# main.net
KiCad netlist of a schematic drawn in EAGLE
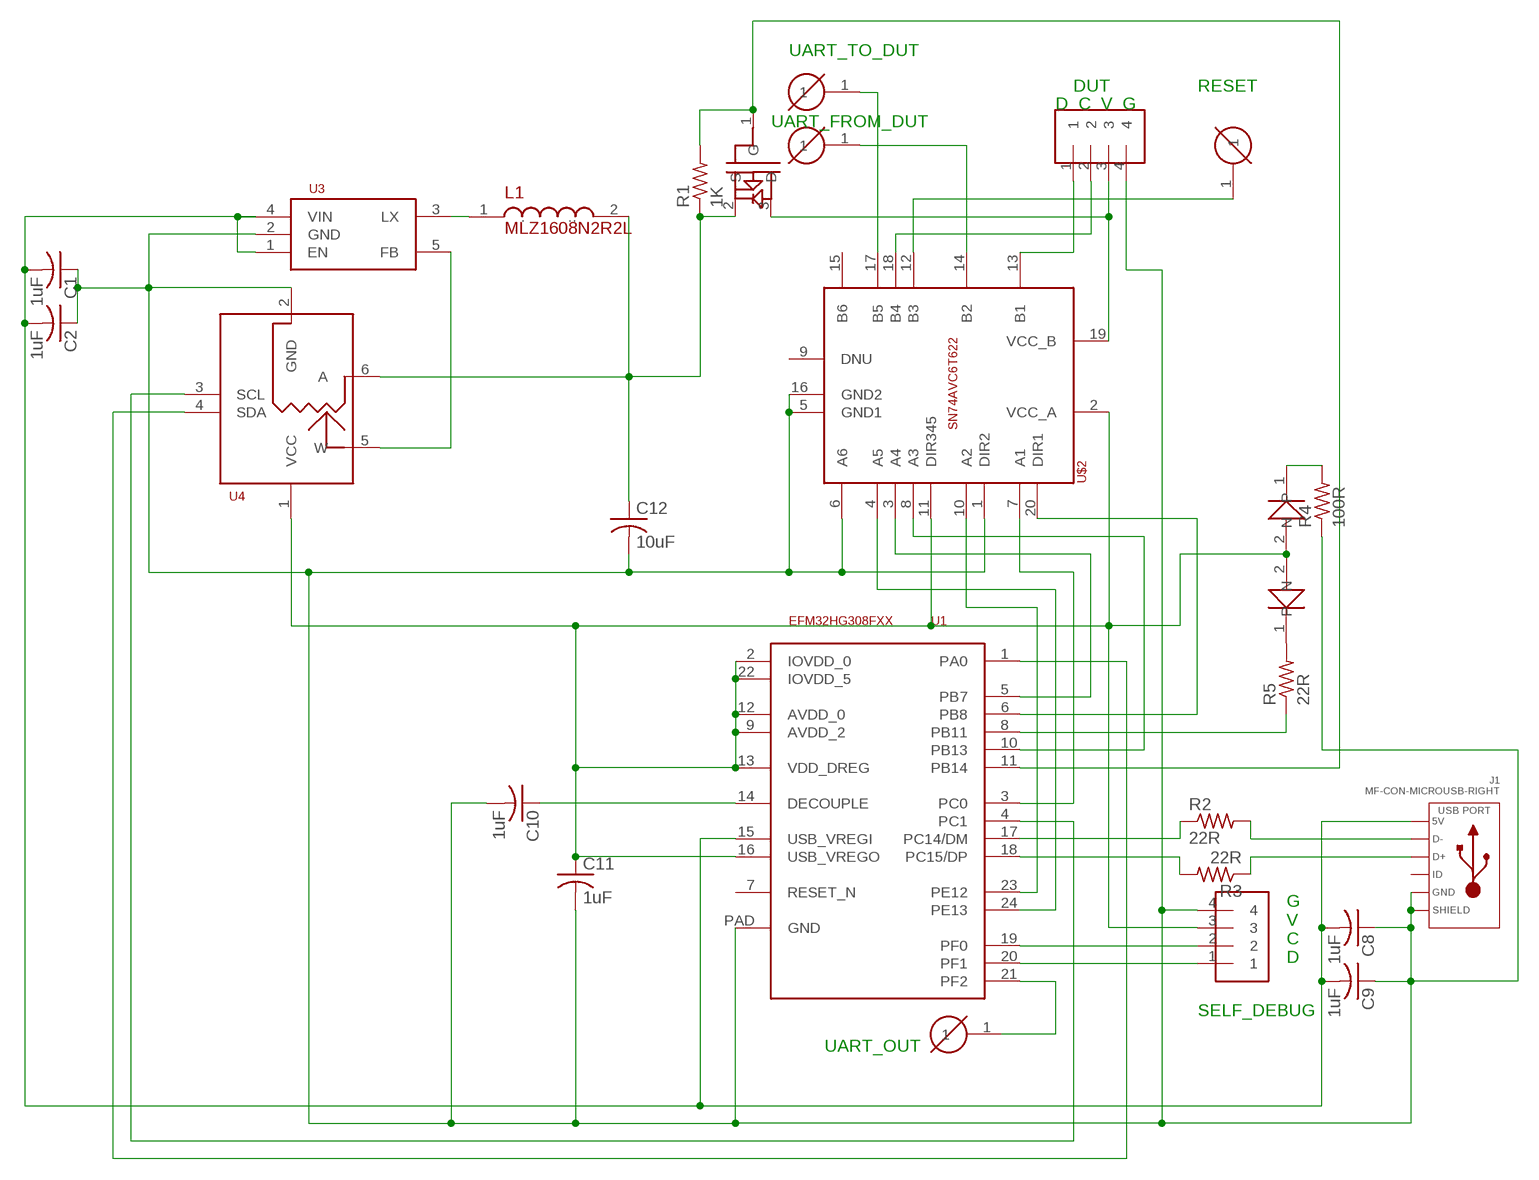
[diagram p0: schematic, sheet 1]

(export (version "E")
  (design (tool "Eeschema 10.0.6"))
  (components
    (comp (ref "C1")
      (value "1uF")
      (footprint "eagle-import:C0402K")
      (libsource (lib "eagle-import") (part "C-USC0402K"))
    )
    (comp (ref "C2")
      (value "1uF")
      (footprint "eagle-import:C0402K")
      (libsource (lib "eagle-import") (part "C-USC0402K"))
    )
    (comp (ref "C8")
      (value "1uF")
      (footprint "eagle-import:C0402K")
      (libsource (lib "eagle-import") (part "C-USC0402K"))
    )
    (comp (ref "C9")
      (value "1uF")
      (footprint "eagle-import:C0402K")
      (libsource (lib "eagle-import") (part "C-USC0402K"))
    )
    (comp (ref "C10")
      (value "1uF")
      (footprint "eagle-import:C0402K")
      (libsource (lib "eagle-import") (part "C-USC0402K"))
    )
    (comp (ref "C11")
      (value "1uF")
      (footprint "eagle-import:C0402K")
      (libsource (lib "eagle-import") (part "C-USC0402K"))
    )
    (comp (ref "C12")
      (value "10uF")
      (footprint "eagle-import:C1206K")
      (libsource (lib "eagle-import") (part "C-USC1206K"))
    )
    (comp (ref "CN_RST")
      (value "PTH_PIN")
      (footprint "eagle-import:PTH_PIN")
      (libsource (lib "eagle-import") (part "PTH_PIN"))
    )
    (comp (ref "CN_RX")
      (value "PTH_PIN")
      (footprint "eagle-import:PTH_PIN")
      (libsource (lib "eagle-import") (part "PTH_PIN"))
    )
    (comp (ref "CN_TX")
      (value "PTH_PIN")
      (footprint "eagle-import:PTH_PIN")
      (libsource (lib "eagle-import") (part "PTH_PIN"))
    )
    (comp (ref "CONN_OUT")
      (value "PIN_HEADER_4X1POLARIZED")
      (footprint "eagle-import:PIN_HEADER_4X1_POLARIZED")
      (libsource (lib "eagle-import") (part "PIN_HEADER_4X1POLARIZED"))
    )
    (comp (ref "CONN_SELF")
      (value "PIN_HEADER_4X1POLARIZED")
      (footprint "eagle-import:PIN_HEADER_4X1_POLARIZED")
      (libsource (lib "eagle-import") (part "PIN_HEADER_4X1POLARIZED"))
    )
    (comp (ref "D1-PWR")
      (value "LED0805")
      (footprint "eagle-import:0805")
      (libsource (lib "eagle-import") (part "LED0805"))
    )
    (comp (ref "D2-ACT")
      (value "LED0805")
      (footprint "eagle-import:0805")
      (libsource (lib "eagle-import") (part "LED0805"))
    )
    (comp (ref "J1")
      (value "MF-CON-MICROUSB-RIGHT")
      (footprint "eagle-import:MICROUSB-RIGHT")
      (fields (field (name "HOUSEPART") "YES"))
      (libsource (lib "eagle-import") (part "USB_MICRO_RIGHT"))
    )
    (comp (ref "L1")
      (value "MLZ1608N2R2L")
      (footprint "eagle-import:0603")
      (libsource (lib "eagle-import") (part "MLZ1608N2R2L"))
    )
    (comp (ref "R1")
      (value "1K")
      (footprint "eagle-import:R0402")
      (libsource (lib "eagle-import") (part "R-US_R0402"))
    )
    (comp (ref "R2")
      (value "22R")
      (footprint "eagle-import:R0402")
      (libsource (lib "eagle-import") (part "R-US_R0402"))
    )
    (comp (ref "R3")
      (value "22R")
      (footprint "eagle-import:R0402")
      (libsource (lib "eagle-import") (part "R-US_R0402"))
    )
    (comp (ref "R4")
      (value "100R")
      (footprint "eagle-import:R0402")
      (libsource (lib "eagle-import") (part "R-US_R0402"))
    )
    (comp (ref "R5")
      (value "22R")
      (footprint "eagle-import:R0402")
      (libsource (lib "eagle-import") (part "R-US_R0402"))
    )
    (comp (ref "TP_UART_OUT")
      (value "PTH_PIN")
      (footprint "eagle-import:PTH_PIN")
      (libsource (lib "eagle-import") (part "PTH_PIN"))
    )
    (comp (ref "U$1")
      (value "PMV50UPE")
      (footprint "eagle-import:SOT23-3")
      (libsource (lib "eagle-import") (part "PMV50UPE"))
    )
    (comp (ref "U$2")
      (value "SN74AVC6T622")
      (footprint "eagle-import:VQFN-20")
      (libsource (lib "eagle-import") (part "SN74AVC6T622"))
    )
    (comp (ref "U1")
      (value "EFM32HG308FXX")
      (footprint "eagle-import:QFN26-0.65")
      (libsource (lib "eagle-import") (part "EFM32HG308FXX"))
    )
    (comp (ref "U3")
      (value "AP3417C")
      (footprint "eagle-import:SOT23")
      (libsource (lib "eagle-import") (part "AP3417C"))
    )
    (comp (ref "U4")
      (value "MCP4018")
      (footprint "eagle-import:SC-70-6")
      (libsource (lib "eagle-import") (part "MCP4018"))
    )
  )
  (nets
    (net (code "1") (name "Net-(D1-PWR-N)") (class "Default")
      (node (ref "D1-PWR") (pin "1") (pinfunction "N_1") (pintype "bidirectional"))
      (node (ref "R4") (pin "2") (pinfunction "2_2") (pintype "passive"))
    )
    (net (code "2") (name "Net-(D1-PWR-P)") (class "Default")
      (node (ref "C11") (pin "1") (pinfunction "1_1") (pintype "passive"))
      (node (ref "CONN_SELF") (pin "3") (pinfunction "3_3") (pintype "bidirectional"))
      (node (ref "D1-PWR") (pin "2") (pinfunction "P_2") (pintype "bidirectional"))
      (node (ref "D2-ACT") (pin "2") (pinfunction "P_2") (pintype "bidirectional"))
      (node (ref "U$2") (pin "11") (pinfunction "DIR345_11") (pintype "bidirectional"))
      (node (ref "U$2") (pin "2") (pinfunction "VCC_A_2") (pintype "bidirectional"))
      (node (ref "U1") (pin "12") (pinfunction "AVDD_0_12") (pintype "bidirectional"))
      (node (ref "U1") (pin "13") (pinfunction "VDD_DREG_13") (pintype "bidirectional"))
      (node (ref "U1") (pin "16") (pinfunction "USB_VREGO_16") (pintype "bidirectional"))
      (node (ref "U1") (pin "2") (pinfunction "IOVDD_0_2") (pintype "bidirectional"))
      (node (ref "U1") (pin "22") (pinfunction "IOVDD_5_22") (pintype "bidirectional"))
      (node (ref "U1") (pin "9") (pinfunction "AVDD_2_9") (pintype "bidirectional"))
      (node (ref "U4") (pin "1") (pinfunction "VCC_1") (pintype "bidirectional"))
    )
    (net (code "3") (name "Net-(D2-ACT-N)") (class "Default")
      (node (ref "D2-ACT") (pin "1") (pinfunction "N_1") (pintype "bidirectional"))
      (node (ref "R5") (pin "2") (pinfunction "2_2") (pintype "passive"))
    )
    (net (code "4") (name "Net-(J1-5V)") (class "Default")
      (node (ref "C1") (pin "2") (pinfunction "2_2") (pintype "passive"))
      (node (ref "C2") (pin "2") (pinfunction "2_2") (pintype "passive"))
      (node (ref "C8") (pin "2") (pinfunction "2_2") (pintype "passive"))
      (node (ref "C9") (pin "2") (pinfunction "2_2") (pintype "passive"))
      (node (ref "J1") (pin "1") (pinfunction "5V_1") (pintype "power_in"))
      (node (ref "U1") (pin "15") (pinfunction "USB_VREGI_15") (pintype "bidirectional"))
      (node (ref "U3") (pin "1") (pinfunction "EN_1") (pintype "bidirectional"))
      (node (ref "U3") (pin "4") (pinfunction "VIN_4") (pintype "bidirectional"))
    )
    (net (code "5") (name "Net-(J1-D+)") (class "Default")
      (node (ref "J1") (pin "3") (pinfunction "D+_3") (pintype "bidirectional"))
      (node (ref "R3") (pin "1") (pinfunction "1_1") (pintype "passive"))
    )
    (net (code "6") (name "Net-(J1-D-)") (class "Default")
      (node (ref "J1") (pin "2") (pinfunction "D-_2") (pintype "bidirectional"))
      (node (ref "R2") (pin "2") (pinfunction "2_2") (pintype "passive"))
    )
    (net (code "7") (name "Net-(J1-GND)") (class "Default")
      (node (ref "C1") (pin "1") (pinfunction "1_1") (pintype "passive"))
      (node (ref "C10") (pin "2") (pinfunction "2_2") (pintype "passive"))
      (node (ref "C11") (pin "2") (pinfunction "2_2") (pintype "passive"))
      (node (ref "C12") (pin "2") (pinfunction "2_2") (pintype "passive"))
      (node (ref "C2") (pin "1") (pinfunction "1_1") (pintype "passive"))
      (node (ref "C8") (pin "1") (pinfunction "1_1") (pintype "passive"))
      (node (ref "C9") (pin "1") (pinfunction "1_1") (pintype "passive"))
      (node (ref "CONN_OUT") (pin "4") (pinfunction "4_4") (pintype "bidirectional"))
      (node (ref "CONN_SELF") (pin "4") (pinfunction "4_4") (pintype "bidirectional"))
      (node (ref "J1") (pin "5") (pinfunction "GND_5") (pintype "power_in"))
      (node (ref "J1") (pin "S1") (pinfunction "SLD_S1") (pintype "power_in"))
      (node (ref "J1") (pin "S2") (pinfunction "SLD_S2") (pintype "power_in"))
      (node (ref "J1") (pin "S3") (pinfunction "SLD_S3") (pintype "power_in"))
      (node (ref "J1") (pin "S4") (pinfunction "SLD_S4") (pintype "power_in"))
      (node (ref "J1") (pin "S5") (pinfunction "SLD_S5") (pintype "power_in"))
      (node (ref "J1") (pin "S6") (pinfunction "SLD_S6") (pintype "power_in"))
      (node (ref "R4") (pin "1") (pinfunction "1_1") (pintype "passive"))
      (node (ref "U$2") (pin "1") (pinfunction "DIR2_1") (pintype "bidirectional"))
      (node (ref "U$2") (pin "16") (pinfunction "GND2_16") (pintype "bidirectional"))
      (node (ref "U$2") (pin "5") (pinfunction "GND1_5") (pintype "bidirectional"))
      (node (ref "U$2") (pin "6") (pinfunction "A6_6") (pintype "bidirectional"))
      (node (ref "U1") (pin "PAD") (pinfunction "GND_PAD") (pintype "bidirectional"))
      (node (ref "U3") (pin "2") (pinfunction "GND_2") (pintype "bidirectional"))
      (node (ref "U4") (pin "2") (pinfunction "GND_2") (pintype "bidirectional"))
    )
    (net (code "8") (name "Net-(L1-.)") (class "Default")
      (node (ref "L1") (pin "1") (pinfunction "._1") (pintype "bidirectional"))
      (node (ref "U3") (pin "3") (pinfunction "LX_3") (pintype "bidirectional"))
    )
    (net (code "9") (name "Net-(L1-..)") (class "Default")
      (node (ref "C12") (pin "1") (pinfunction "1_1") (pintype "passive"))
      (node (ref "L1") (pin "2") (pinfunction ".._2") (pintype "bidirectional"))
      (node (ref "R1") (pin "1") (pinfunction "1_1") (pintype "passive"))
      (node (ref "U$1") (pin "2") (pinfunction "S_2") (pintype "bidirectional"))
      (node (ref "U4") (pin "6") (pinfunction "A_6") (pintype "bidirectional"))
    )
    (net (code "10") (name "Net-(U$1-D)") (class "Default")
      (node (ref "CONN_OUT") (pin "3") (pinfunction "3_3") (pintype "bidirectional"))
      (node (ref "U$1") (pin "3") (pinfunction "D_3") (pintype "bidirectional"))
      (node (ref "U$2") (pin "19") (pinfunction "VCC_B_19") (pintype "bidirectional"))
    )
    (net (code "11") (name "Net-(U$1-G)") (class "Default")
      (node (ref "R1") (pin "2") (pinfunction "2_2") (pintype "passive"))
      (node (ref "U$1") (pin "1") (pinfunction "G_1") (pintype "bidirectional"))
      (node (ref "U1") (pin "11") (pinfunction "PB14_11") (pintype "bidirectional"))
    )
    (net (code "12") (name "Net-(U$2-A1)") (class "Default")
      (node (ref "U$2") (pin "7") (pinfunction "A1_7") (pintype "bidirectional"))
      (node (ref "U1") (pin "3") (pinfunction "PC0_3") (pintype "bidirectional"))
    )
    (net (code "13") (name "Net-(U$2-A2)") (class "Default")
      (node (ref "U$2") (pin "10") (pinfunction "A2_10") (pintype "bidirectional"))
      (node (ref "U1") (pin "23") (pinfunction "PE12_23") (pintype "bidirectional"))
    )
    (net (code "14") (name "Net-(U$2-A3)") (class "Default")
      (node (ref "U$2") (pin "8") (pinfunction "A3_8") (pintype "bidirectional"))
      (node (ref "U1") (pin "10") (pinfunction "PB13_10") (pintype "bidirectional"))
    )
    (net (code "15") (name "Net-(U$2-A4)") (class "Default")
      (node (ref "U$2") (pin "3") (pinfunction "A4_3") (pintype "bidirectional"))
      (node (ref "U1") (pin "5") (pinfunction "PB7_5") (pintype "bidirectional"))
    )
    (net (code "16") (name "Net-(U$2-A5)") (class "Default")
      (node (ref "U$2") (pin "4") (pinfunction "A5_4") (pintype "bidirectional"))
      (node (ref "U1") (pin "24") (pinfunction "PE13_24") (pintype "bidirectional"))
    )
    (net (code "17") (name "Net-(U$2-B1)") (class "Default")
      (node (ref "CONN_OUT") (pin "1") (pinfunction "1_1") (pintype "bidirectional"))
      (node (ref "U$2") (pin "13") (pinfunction "B1_13") (pintype "bidirectional"))
    )
    (net (code "18") (name "Net-(U$2-B2)") (class "Default")
      (node (ref "CN_RX") (pin "1") (pinfunction "1_1") (pintype "bidirectional"))
      (node (ref "U$2") (pin "14") (pinfunction "B2_14") (pintype "bidirectional"))
    )
    (net (code "19") (name "Net-(U$2-B3)") (class "Default")
      (node (ref "CN_RST") (pin "1") (pinfunction "1_1") (pintype "bidirectional"))
      (node (ref "U$2") (pin "12") (pinfunction "B3_12") (pintype "bidirectional"))
    )
    (net (code "20") (name "Net-(U$2-B4)") (class "Default")
      (node (ref "CONN_OUT") (pin "2") (pinfunction "2_2") (pintype "bidirectional"))
      (node (ref "U$2") (pin "18") (pinfunction "B4_18") (pintype "bidirectional"))
    )
    (net (code "21") (name "Net-(U$2-B5)") (class "Default")
      (node (ref "CN_TX") (pin "1") (pinfunction "1_1") (pintype "bidirectional"))
      (node (ref "U$2") (pin "17") (pinfunction "B5_17") (pintype "bidirectional"))
    )
    (net (code "22") (name "Net-(U$2-DIR1)") (class "Default")
      (node (ref "U$2") (pin "20") (pinfunction "DIR1_20") (pintype "bidirectional"))
      (node (ref "U1") (pin "6") (pinfunction "PB8_6") (pintype "bidirectional"))
    )
    (net (code "23") (name "Net-(U1-DECOUPLE)") (class "Default")
      (node (ref "C10") (pin "1") (pinfunction "1_1") (pintype "passive"))
      (node (ref "U1") (pin "14") (pinfunction "DECOUPLE_14") (pintype "bidirectional"))
    )
    (net (code "24") (name "Net-(U1-PA0)") (class "Default")
      (node (ref "U1") (pin "1") (pinfunction "PA0_1") (pintype "bidirectional"))
      (node (ref "U4") (pin "4") (pinfunction "SDA_4") (pintype "bidirectional"))
    )
    (net (code "25") (name "Net-(U1-PB11)") (class "Default")
      (node (ref "R5") (pin "1") (pinfunction "1_1") (pintype "passive"))
      (node (ref "U1") (pin "8") (pinfunction "PB11_8") (pintype "bidirectional"))
    )
    (net (code "26") (name "Net-(U1-PC1)") (class "Default")
      (node (ref "U1") (pin "4") (pinfunction "PC1_4") (pintype "bidirectional"))
      (node (ref "U4") (pin "3") (pinfunction "SCL_3") (pintype "bidirectional"))
    )
    (net (code "27") (name "Net-(U1-PC14{slash}DM)") (class "Default")
      (node (ref "R2") (pin "1") (pinfunction "1_1") (pintype "passive"))
      (node (ref "U1") (pin "17") (pinfunction "PC14/DM_17") (pintype "bidirectional"))
    )
    (net (code "28") (name "Net-(U1-PC15{slash}DP)") (class "Default")
      (node (ref "R3") (pin "2") (pinfunction "2_2") (pintype "passive"))
      (node (ref "U1") (pin "18") (pinfunction "PC15/DP_18") (pintype "bidirectional"))
    )
    (net (code "29") (name "Net-(U1-PF0)") (class "Default")
      (node (ref "CONN_SELF") (pin "2") (pinfunction "2_2") (pintype "bidirectional"))
      (node (ref "U1") (pin "19") (pinfunction "PF0_19") (pintype "bidirectional"))
    )
    (net (code "30") (name "Net-(U1-PF1)") (class "Default")
      (node (ref "CONN_SELF") (pin "1") (pinfunction "1_1") (pintype "bidirectional"))
      (node (ref "U1") (pin "20") (pinfunction "PF1_20") (pintype "bidirectional"))
    )
    (net (code "31") (name "Net-(U1-PF2)") (class "Default")
      (node (ref "TP_UART_OUT") (pin "1") (pinfunction "1_1") (pintype "bidirectional"))
      (node (ref "U1") (pin "21") (pinfunction "PF2_21") (pintype "bidirectional"))
    )
    (net (code "32") (name "Net-(U3-FB)") (class "Default")
      (node (ref "U3") (pin "5") (pinfunction "FB_5") (pintype "bidirectional"))
      (node (ref "U4") (pin "5") (pinfunction "W_5") (pintype "bidirectional"))
    )
    (net (code "33") (name "unconnected-(J1-ID-Pad4)") (class "Default")
      (node (ref "J1") (pin "4") (pinfunction "ID_4") (pintype "bidirectional"))
    )
    (net (code "34") (name "unconnected-(U$2-B6-Pad15)") (class "Default")
      (node (ref "U$2") (pin "15") (pinfunction "B6_15") (pintype "bidirectional"))
    )
    (net (code "35") (name "unconnected-(U$2-DNU-Pad9)") (class "Default")
      (node (ref "U$2") (pin "9") (pinfunction "DNU_9") (pintype "bidirectional"))
    )
    (net (code "36") (name "unconnected-(U1-RESET_N-Pad7)") (class "Default")
      (node (ref "U1") (pin "7") (pinfunction "RESET_N_7") (pintype "bidirectional"))
    )
  )
)
